# BB8_PCB.net
KiCad netlist of a schematic drawn in EAGLE
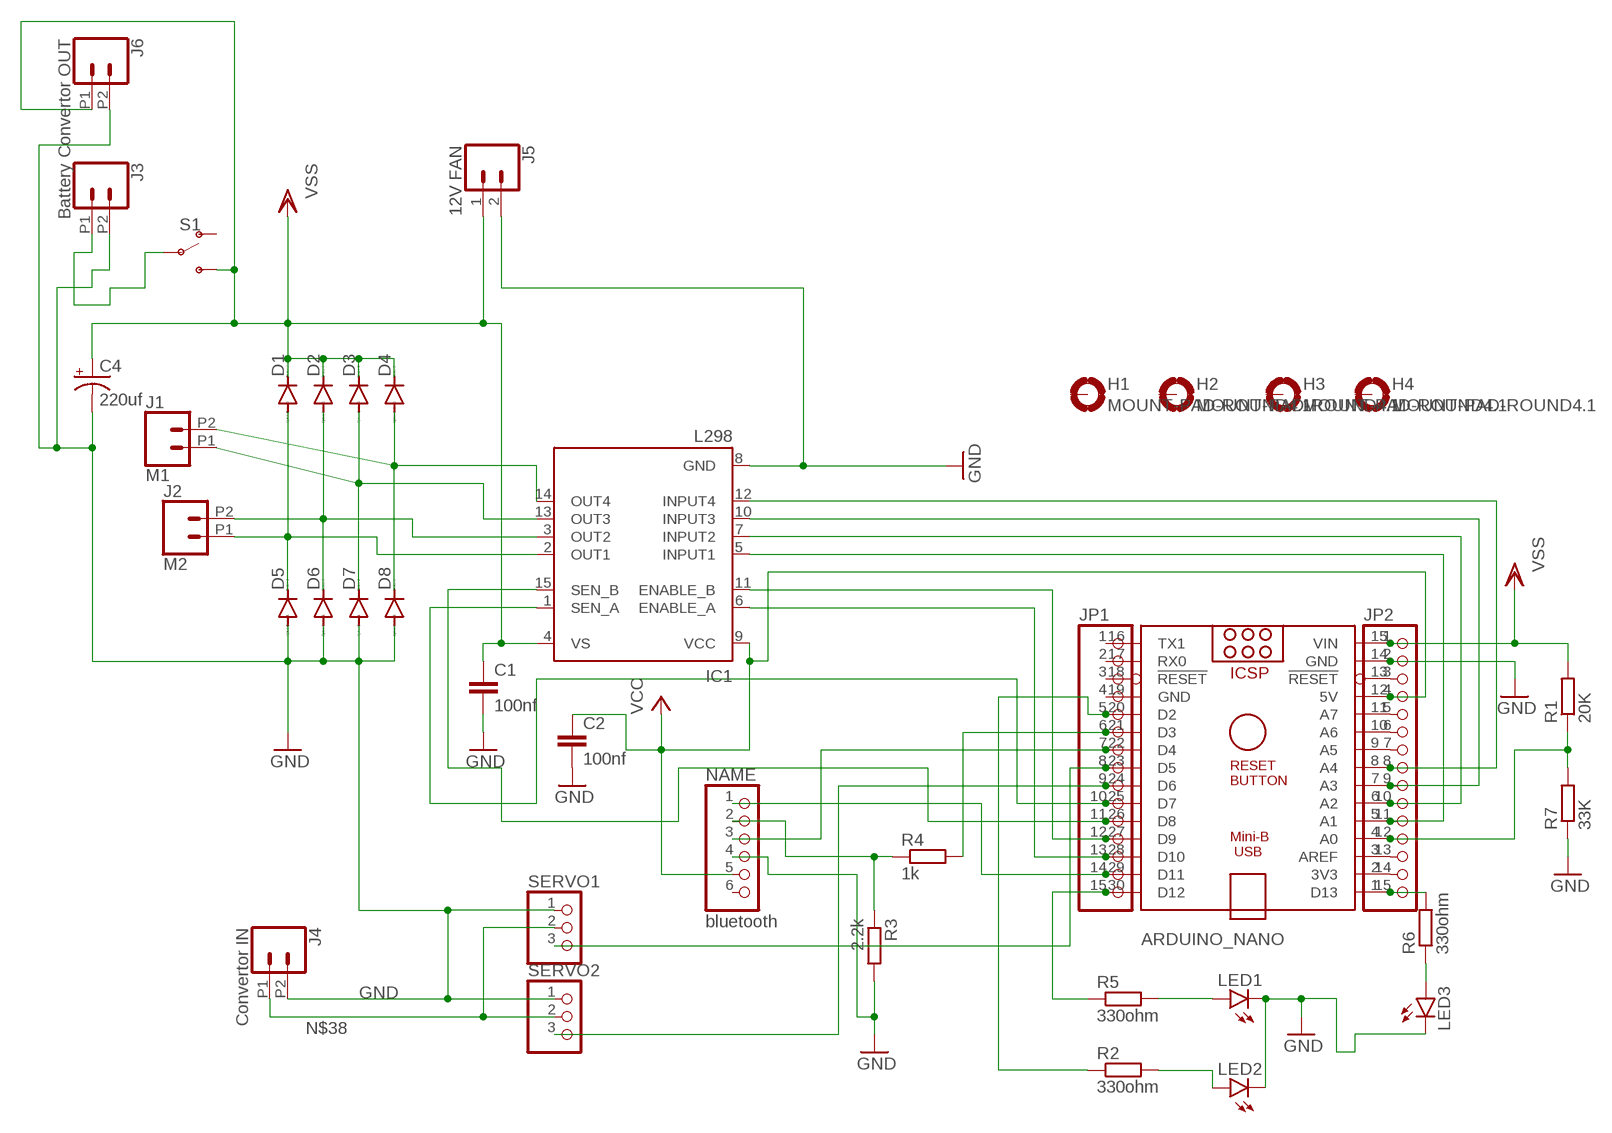
[diagram p0: schematic, sheet 1]

(export (version "E")
  (design (tool "Eeschema 10.0.6"))
  (components
    (comp (ref "ARDUINO_NANO")
      (value "ARDUINO_NANO")
      (footprint "eagle-import:ARDUINO_NANO")
      (libsource (lib "eagle-import") (part "ARDUINO_NANO"))
    )
    (comp (ref "BLUETOOTH")
      (value "bluetooth")
      (footprint "eagle-import:1X06")
      (libsource (lib "eagle-import") (part "PINHD-1X6"))
    )
    (comp (ref "C1")
      (value "100nf")
      (footprint "eagle-import:C5B2.5")
      (libsource (lib "eagle-import") (part "C5/2.5"))
    )
    (comp (ref "C2")
      (value "100nf")
      (footprint "eagle-import:C5B2.5")
      (libsource (lib "eagle-import") (part "C5/2.5"))
    )
    (comp (ref "C4")
      (value "220uf")
      (footprint "eagle-import:E5-8,5")
      (libsource (lib "eagle-import") (part "CPOL-USE5-8.5"))
    )
    (comp (ref "D1")
      (value "1N4148DO35-7")
      (footprint "eagle-import:DO35-7")
      (libsource (lib "eagle-import") (part "1N4148DO35-7"))
    )
    (comp (ref "D2")
      (value "1N4148DO35-7")
      (footprint "eagle-import:DO35-7")
      (libsource (lib "eagle-import") (part "1N4148DO35-7"))
    )
    (comp (ref "D3")
      (value "1N4148DO35-7")
      (footprint "eagle-import:DO35-7")
      (libsource (lib "eagle-import") (part "1N4148DO35-7"))
    )
    (comp (ref "D4")
      (value "1N4148DO35-7")
      (footprint "eagle-import:DO35-7")
      (libsource (lib "eagle-import") (part "1N4148DO35-7"))
    )
    (comp (ref "D5")
      (value "1N4148DO35-7")
      (footprint "eagle-import:DO35-7")
      (libsource (lib "eagle-import") (part "1N4148DO35-7"))
    )
    (comp (ref "D6")
      (value "1N4148DO35-7")
      (footprint "eagle-import:DO35-7")
      (libsource (lib "eagle-import") (part "1N4148DO35-7"))
    )
    (comp (ref "D7")
      (value "1N4148DO35-7")
      (footprint "eagle-import:DO35-7")
      (libsource (lib "eagle-import") (part "1N4148DO35-7"))
    )
    (comp (ref "D8")
      (value "1N4148DO35-7")
      (footprint "eagle-import:DO35-7")
      (libsource (lib "eagle-import") (part "1N4148DO35-7"))
    )
    (comp (ref "H1")
      (value "MOUNT-PAD-ROUND4.1")
      (footprint "eagle-import:4,1-PAD")
      (libsource (lib "eagle-import") (part "MOUNT-PAD-ROUND4.1"))
    )
    (comp (ref "H2")
      (value "MOUNT-PAD-ROUND4.1")
      (footprint "eagle-import:4,1-PAD")
      (libsource (lib "eagle-import") (part "MOUNT-PAD-ROUND4.1"))
    )
    (comp (ref "H3")
      (value "MOUNT-PAD-ROUND4.1")
      (footprint "eagle-import:4,1-PAD")
      (libsource (lib "eagle-import") (part "MOUNT-PAD-ROUND4.1"))
    )
    (comp (ref "H4")
      (value "MOUNT-PAD-ROUND4.1")
      (footprint "eagle-import:4,1-PAD")
      (libsource (lib "eagle-import") (part "MOUNT-PAD-ROUND4.1"))
    )
    (comp (ref "IC1")
      (value "L298")
      (footprint "eagle-import:MULTIWATT-15")
      (fields (field (name "MPN") "L298N"))
      (libsource (lib "eagle-import") (part "L298"))
    )
    (comp (ref "J1")
      (value "M1")
      (footprint "eagle-import:1X02_2.54_SCREWTERM")
      (libsource (lib "eagle-import") (part "CONN_022.54MM_SCREWTERM"))
    )
    (comp (ref "J2")
      (value "M2")
      (footprint "eagle-import:1X02_2.54_SCREWTERM")
      (libsource (lib "eagle-import") (part "CONN_022.54MM_SCREWTERM"))
    )
    (comp (ref "J3")
      (value "Battery")
      (footprint "eagle-import:1X02_2.54_SCREWTERM")
      (libsource (lib "eagle-import") (part "CONN_022.54MM_SCREWTERM"))
    )
    (comp (ref "J4")
      (value "Convertor IN")
      (footprint "eagle-import:1X02_2.54_SCREWTERM")
      (libsource (lib "eagle-import") (part "CONN_022.54MM_SCREWTERM"))
    )
    (comp (ref "J5")
      (value "12V FAN")
      (footprint "eagle-import:1X02")
      (libsource (lib "eagle-import") (part "CONN_02"))
    )
    (comp (ref "J6")
      (value "Convertor OUT")
      (footprint "eagle-import:1X02_2.54_SCREWTERM")
      (libsource (lib "eagle-import") (part "CONN_022.54MM_SCREWTERM"))
    )
    (comp (ref "JP1")
      (value "PINHD-1X15")
      (footprint "eagle-import:1X15")
      (libsource (lib "eagle-import") (part "PINHD-1X15"))
    )
    (comp (ref "JP2")
      (value "PINHD-1X15")
      (footprint "eagle-import:1X15")
      (libsource (lib "eagle-import") (part "PINHD-1X15"))
    )
    (comp (ref "LED1")
      (value "LED5MM")
      (footprint "eagle-import:LED5MM")
      (libsource (lib "eagle-import") (part "LED5MM"))
    )
    (comp (ref "LED2")
      (value "LED5MM")
      (footprint "eagle-import:LED5MM")
      (libsource (lib "eagle-import") (part "LED5MM"))
    )
    (comp (ref "LED3")
      (value "LED5MM")
      (footprint "eagle-import:LED5MM")
      (libsource (lib "eagle-import") (part "LED5MM"))
    )
    (comp (ref "R1")
      (value "20K")
      (footprint "eagle-import:0204_7")
      (libsource (lib "eagle-import") (part "R-EU_0204/7"))
    )
    (comp (ref "R2")
      (value "330ohm")
      (footprint "eagle-import:0204_7")
      (libsource (lib "eagle-import") (part "R-EU_0204/7"))
    )
    (comp (ref "R3")
      (value "2.2k")
      (footprint "eagle-import:0204_7")
      (libsource (lib "eagle-import") (part "R-EU_0204/7"))
    )
    (comp (ref "R4")
      (value "1k")
      (footprint "eagle-import:0204_7")
      (libsource (lib "eagle-import") (part "R-EU_0204/7"))
    )
    (comp (ref "R5")
      (value "330ohm")
      (footprint "eagle-import:0204_7")
      (libsource (lib "eagle-import") (part "R-EU_0204/7"))
    )
    (comp (ref "R6")
      (value "330ohm")
      (footprint "eagle-import:0204_7")
      (libsource (lib "eagle-import") (part "R-EU_0204/7"))
    )
    (comp (ref "R7")
      (value "33K")
      (footprint "eagle-import:0204_7")
      (libsource (lib "eagle-import") (part "R-EU_0204/7"))
    )
    (comp (ref "S1")
      (value "SWITCH-SPDT-PTH-11.6X4.0MM-LOCK")
      (footprint "eagle-import:SWITCH_SPDT_PTH_11.6X4.0MM_LOCK")
      (libsource (lib "eagle-import") (part "SWITCH-SPDT-PTH-11.6X4.0MM-LOCK"))
    )
    (comp (ref "SERVO1")
      (value "PINHD-1X3")
      (footprint "eagle-import:1X03")
      (libsource (lib "eagle-import") (part "PINHD-1X3"))
    )
    (comp (ref "SERVO2")
      (value "PINHD-1X3")
      (footprint "eagle-import:1X03")
      (libsource (lib "eagle-import") (part "PINHD-1X3"))
    )
  )
  (nets
    (net (code "1") (name "/N$38") (class "Default")
      (node (ref "J4") (pin "P1") (pinfunction "1_P1") (pintype "passive"))
      (node (ref "SERVO1") (pin "2") (pinfunction "2_2") (pintype "passive"))
      (node (ref "SERVO2") (pin "2") (pinfunction "2_2") (pintype "passive"))
    )
    (net (code "2") (name "GND") (class "Default")
      (node (ref "ARDUINO_NANO") (pin "14") (pinfunction "GND_14") (pintype "power_in"))
      (node (ref "BLUETOOTH") (pin "4") (pinfunction "4_4") (pintype "passive"))
      (node (ref "C1") (pin "2") (pinfunction "2_2") (pintype "passive"))
      (node (ref "C2") (pin "2") (pinfunction "2_2") (pintype "passive"))
      (node (ref "C4") (pin "-") (pinfunction "-_-") (pintype "passive"))
      (node (ref "D5") (pin "A") (pinfunction "A_A") (pintype "passive"))
      (node (ref "D6") (pin "A") (pinfunction "A_A") (pintype "passive"))
      (node (ref "D7") (pin "A") (pinfunction "A_A") (pintype "passive"))
      (node (ref "D8") (pin "A") (pinfunction "A_A") (pintype "passive"))
      (node (ref "IC1") (pin "8") (pinfunction "GND_8") (pintype "power_in"))
      (node (ref "J3") (pin "P2") (pinfunction "2_P2") (pintype "passive"))
      (node (ref "J4") (pin "P2") (pinfunction "2_P2") (pintype "passive"))
      (node (ref "J5") (pin "2") (pinfunction "2_2") (pintype "passive"))
      (node (ref "J6") (pin "P2") (pinfunction "2_P2") (pintype "passive"))
      (node (ref "JP2") (pin "2") (pinfunction "2_2") (pintype "passive"))
      (node (ref "LED1") (pin "K") (pinfunction "C_K") (pintype "passive"))
      (node (ref "LED2") (pin "K") (pinfunction "C_K") (pintype "passive"))
      (node (ref "LED3") (pin "K") (pinfunction "C_K") (pintype "passive"))
      (node (ref "R3") (pin "2") (pinfunction "2_2") (pintype "passive"))
      (node (ref "R7") (pin "1") (pinfunction "1_1") (pintype "passive"))
      (node (ref "SERVO1") (pin "1") (pinfunction "1_1") (pintype "passive"))
      (node (ref "SERVO2") (pin "1") (pinfunction "1_1") (pintype "passive"))
    )
    (net (code "3") (name "Net-(ARDUINO_NANO-3V3)") (class "Default")
      (node (ref "ARDUINO_NANO") (pin "2") (pinfunction "3V3_2") (pintype "output"))
      (node (ref "JP2") (pin "14") (pinfunction "14_14") (pintype "passive"))
    )
    (net (code "4") (name "Net-(ARDUINO_NANO-A0)") (class "Default")
      (node (ref "ARDUINO_NANO") (pin "4") (pinfunction "A0_4") (pintype "bidirectional"))
      (node (ref "JP2") (pin "12") (pinfunction "12_12") (pintype "passive"))
      (node (ref "R1") (pin "1") (pinfunction "1_1") (pintype "passive"))
      (node (ref "R7") (pin "2") (pinfunction "2_2") (pintype "passive"))
    )
    (net (code "5") (name "Net-(ARDUINO_NANO-A1)") (class "Default")
      (node (ref "ARDUINO_NANO") (pin "5") (pinfunction "A1_5") (pintype "bidirectional"))
      (node (ref "IC1") (pin "5") (pinfunction "INPUT1_5") (pintype "input"))
      (node (ref "JP2") (pin "11") (pinfunction "11_11") (pintype "passive"))
    )
    (net (code "6") (name "Net-(ARDUINO_NANO-A2)") (class "Default")
      (node (ref "ARDUINO_NANO") (pin "6") (pinfunction "A2_6") (pintype "bidirectional"))
      (node (ref "IC1") (pin "7") (pinfunction "INPUT2_7") (pintype "input"))
      (node (ref "JP2") (pin "10") (pinfunction "10_10") (pintype "passive"))
    )
    (net (code "7") (name "Net-(ARDUINO_NANO-A3)") (class "Default")
      (node (ref "ARDUINO_NANO") (pin "7") (pinfunction "A3_7") (pintype "bidirectional"))
      (node (ref "IC1") (pin "10") (pinfunction "INPUT3_10") (pintype "input"))
      (node (ref "JP2") (pin "9") (pinfunction "9_9") (pintype "passive"))
    )
    (net (code "8") (name "Net-(ARDUINO_NANO-A4)") (class "Default")
      (node (ref "ARDUINO_NANO") (pin "8") (pinfunction "A4_8") (pintype "bidirectional"))
      (node (ref "IC1") (pin "12") (pinfunction "INPUT4_12") (pintype "input"))
      (node (ref "JP2") (pin "8") (pinfunction "8_8") (pintype "passive"))
    )
    (net (code "9") (name "Net-(ARDUINO_NANO-A5)") (class "Default")
      (node (ref "ARDUINO_NANO") (pin "9") (pinfunction "A5_9") (pintype "bidirectional"))
      (node (ref "JP2") (pin "7") (pinfunction "7_7") (pintype "passive"))
    )
    (net (code "10") (name "Net-(ARDUINO_NANO-A6)") (class "Default")
      (node (ref "ARDUINO_NANO") (pin "10") (pinfunction "A6_10") (pintype "bidirectional"))
      (node (ref "JP2") (pin "6") (pinfunction "6_6") (pintype "passive"))
    )
    (net (code "11") (name "Net-(ARDUINO_NANO-A7)") (class "Default")
      (node (ref "ARDUINO_NANO") (pin "11") (pinfunction "A7_11") (pintype "bidirectional"))
      (node (ref "JP2") (pin "5") (pinfunction "5_5") (pintype "passive"))
    )
    (net (code "12") (name "Net-(ARDUINO_NANO-AREF)") (class "Default")
      (node (ref "ARDUINO_NANO") (pin "3") (pinfunction "AREF_3") (pintype "input"))
      (node (ref "JP2") (pin "13") (pinfunction "13_13") (pintype "passive"))
    )
    (net (code "13") (name "Net-(ARDUINO_NANO-D2)") (class "Default")
      (node (ref "ARDUINO_NANO") (pin "20") (pinfunction "D2_20") (pintype "bidirectional"))
      (node (ref "JP1") (pin "5") (pinfunction "5_5") (pintype "passive"))
      (node (ref "R2") (pin "1") (pinfunction "1_1") (pintype "passive"))
    )
    (net (code "14") (name "Net-(ARDUINO_NANO-D3)") (class "Default")
      (node (ref "ARDUINO_NANO") (pin "21") (pinfunction "D3_21") (pintype "bidirectional"))
      (node (ref "JP1") (pin "6") (pinfunction "6_6") (pintype "passive"))
      (node (ref "R4") (pin "2") (pinfunction "2_2") (pintype "passive"))
    )
    (net (code "15") (name "Net-(ARDUINO_NANO-D4)") (class "Default")
      (node (ref "ARDUINO_NANO") (pin "22") (pinfunction "D4_22") (pintype "bidirectional"))
      (node (ref "BLUETOOTH") (pin "3") (pinfunction "3_3") (pintype "passive"))
      (node (ref "JP1") (pin "7") (pinfunction "7_7") (pintype "passive"))
    )
    (net (code "16") (name "Net-(ARDUINO_NANO-D5)") (class "Default")
      (node (ref "ARDUINO_NANO") (pin "23") (pinfunction "D5_23") (pintype "bidirectional"))
      (node (ref "JP1") (pin "8") (pinfunction "8_8") (pintype "passive"))
      (node (ref "SERVO1") (pin "3") (pinfunction "3_3") (pintype "passive"))
    )
    (net (code "17") (name "Net-(ARDUINO_NANO-D6)") (class "Default")
      (node (ref "ARDUINO_NANO") (pin "24") (pinfunction "D6_24") (pintype "bidirectional"))
      (node (ref "JP1") (pin "9") (pinfunction "9_9") (pintype "passive"))
      (node (ref "SERVO2") (pin "3") (pinfunction "3_3") (pintype "passive"))
    )
    (net (code "18") (name "Net-(ARDUINO_NANO-D7)") (class "Default")
      (node (ref "ARDUINO_NANO") (pin "25") (pinfunction "D7_25") (pintype "bidirectional"))
      (node (ref "IC1") (pin "1") (pinfunction "SEN_A_1") (pintype "input"))
      (node (ref "JP1") (pin "10") (pinfunction "10_10") (pintype "passive"))
    )
    (net (code "19") (name "Net-(ARDUINO_NANO-D8)") (class "Default")
      (node (ref "ARDUINO_NANO") (pin "26") (pinfunction "D8_26") (pintype "bidirectional"))
      (node (ref "IC1") (pin "15") (pinfunction "SEN_B_15") (pintype "input"))
      (node (ref "JP1") (pin "11") (pinfunction "11_11") (pintype "passive"))
    )
    (net (code "20") (name "Net-(ARDUINO_NANO-D9)") (class "Default")
      (node (ref "ARDUINO_NANO") (pin "27") (pinfunction "D9_27") (pintype "bidirectional"))
      (node (ref "IC1") (pin "11") (pinfunction "ENABLE_B_11") (pintype "input"))
      (node (ref "JP1") (pin "12") (pinfunction "12_12") (pintype "passive"))
    )
    (net (code "21") (name "Net-(ARDUINO_NANO-D10)") (class "Default")
      (node (ref "ARDUINO_NANO") (pin "28") (pinfunction "D10_28") (pintype "bidirectional"))
      (node (ref "IC1") (pin "6") (pinfunction "ENABLE_A_6") (pintype "input"))
      (node (ref "JP1") (pin "13") (pinfunction "13_13") (pintype "passive"))
    )
    (net (code "22") (name "Net-(ARDUINO_NANO-D11)") (class "Default")
      (node (ref "ARDUINO_NANO") (pin "29") (pinfunction "D11_29") (pintype "bidirectional"))
      (node (ref "BLUETOOTH") (pin "1") (pinfunction "1_1") (pintype "passive"))
      (node (ref "JP1") (pin "14") (pinfunction "14_14") (pintype "passive"))
    )
    (net (code "23") (name "Net-(ARDUINO_NANO-D12)") (class "Default")
      (node (ref "ARDUINO_NANO") (pin "30") (pinfunction "D12_30") (pintype "bidirectional"))
      (node (ref "JP1") (pin "15") (pinfunction "15_15") (pintype "passive"))
      (node (ref "R5") (pin "1") (pinfunction "1_1") (pintype "passive"))
    )
    (net (code "24") (name "Net-(ARDUINO_NANO-D13)") (class "Default")
      (node (ref "ARDUINO_NANO") (pin "1") (pinfunction "D13_1") (pintype "bidirectional"))
      (node (ref "JP2") (pin "15") (pinfunction "15_15") (pintype "passive"))
      (node (ref "R6") (pin "2") (pinfunction "2_2") (pintype "passive"))
    )
    (net (code "25") (name "Net-(ARDUINO_NANO-GND-Pad19)") (class "Default")
      (node (ref "ARDUINO_NANO") (pin "19") (pinfunction "GND_19") (pintype "power_in"))
      (node (ref "JP1") (pin "4") (pinfunction "4_4") (pintype "passive"))
    )
    (net (code "26") (name "Net-(ARDUINO_NANO-RX0)") (class "Default")
      (node (ref "ARDUINO_NANO") (pin "17") (pinfunction "RX0_17") (pintype "bidirectional"))
      (node (ref "JP1") (pin "2") (pinfunction "2_2") (pintype "passive"))
    )
    (net (code "27") (name "Net-(ARDUINO_NANO-TX1)") (class "Default")
      (node (ref "ARDUINO_NANO") (pin "16") (pinfunction "TX1_16") (pintype "bidirectional"))
      (node (ref "JP1") (pin "1") (pinfunction "1_1") (pintype "passive"))
    )
    (net (code "28") (name "Net-(ARDUINO_NANO-~{RESET}-Pad13)") (class "Default")
      (node (ref "ARDUINO_NANO") (pin "13") (pinfunction "~{RESET}_13") (pintype "input"))
      (node (ref "JP2") (pin "3") (pinfunction "3_3") (pintype "passive"))
    )
    (net (code "29") (name "Net-(ARDUINO_NANO-~{RESET}-Pad18)") (class "Default")
      (node (ref "ARDUINO_NANO") (pin "18") (pinfunction "~{RESET}_18") (pintype "input"))
      (node (ref "JP1") (pin "3") (pinfunction "3_3") (pintype "passive"))
    )
    (net (code "30") (name "Net-(BLUETOOTH-Pad2)") (class "Default")
      (node (ref "BLUETOOTH") (pin "2") (pinfunction "2_2") (pintype "passive"))
      (node (ref "R3") (pin "1") (pinfunction "1_1") (pintype "passive"))
      (node (ref "R4") (pin "1") (pinfunction "1_1") (pintype "passive"))
    )
    (net (code "31") (name "Net-(IC1-OUT1)") (class "Default")
      (node (ref "D1") (pin "A") (pinfunction "A_A") (pintype "passive"))
      (node (ref "D5") (pin "C") (pinfunction "C_C") (pintype "passive"))
      (node (ref "IC1") (pin "2") (pinfunction "OUT1_2") (pintype "output"))
      (node (ref "J2") (pin "P1") (pinfunction "1_P1") (pintype "passive"))
    )
    (net (code "32") (name "Net-(IC1-OUT2)") (class "Default")
      (node (ref "D2") (pin "A") (pinfunction "A_A") (pintype "passive"))
      (node (ref "D6") (pin "C") (pinfunction "C_C") (pintype "passive"))
      (node (ref "IC1") (pin "3") (pinfunction "OUT2_3") (pintype "output"))
      (node (ref "J2") (pin "P2") (pinfunction "2_P2") (pintype "passive"))
    )
    (net (code "33") (name "Net-(IC1-OUT3)") (class "Default")
      (node (ref "D3") (pin "A") (pinfunction "A_A") (pintype "passive"))
      (node (ref "D7") (pin "C") (pinfunction "C_C") (pintype "passive"))
      (node (ref "IC1") (pin "13") (pinfunction "OUT3_13") (pintype "output"))
      (node (ref "J1") (pin "P1") (pinfunction "1_P1") (pintype "passive"))
    )
    (net (code "34") (name "Net-(IC1-OUT4)") (class "Default")
      (node (ref "D4") (pin "A") (pinfunction "A_A") (pintype "passive"))
      (node (ref "D8") (pin "C") (pinfunction "C_C") (pintype "passive"))
      (node (ref "IC1") (pin "14") (pinfunction "OUT4_14") (pintype "output"))
      (node (ref "J1") (pin "P2") (pinfunction "2_P2") (pintype "passive"))
    )
    (net (code "35") (name "Net-(J3-1)") (class "Default")
      (node (ref "J3") (pin "P1") (pinfunction "1_P1") (pintype "passive"))
      (node (ref "S1") (pin "2") (pinfunction "P_2") (pintype "passive"))
    )
    (net (code "36") (name "Net-(LED1-PadA)") (class "Default")
      (node (ref "LED1") (pin "A") (pinfunction "A_A") (pintype "passive"))
      (node (ref "R5") (pin "2") (pinfunction "2_2") (pintype "passive"))
    )
    (net (code "37") (name "Net-(LED2-PadA)") (class "Default")
      (node (ref "LED2") (pin "A") (pinfunction "A_A") (pintype "passive"))
      (node (ref "R2") (pin "2") (pinfunction "2_2") (pintype "passive"))
    )
    (net (code "38") (name "Net-(LED3-PadA)") (class "Default")
      (node (ref "LED3") (pin "A") (pinfunction "A_A") (pintype "passive"))
      (node (ref "R6") (pin "1") (pinfunction "1_1") (pintype "passive"))
    )
    (net (code "39") (name "VCC") (class "Default")
      (node (ref "ARDUINO_NANO") (pin "12") (pinfunction "5V_12") (pintype "power_in"))
      (node (ref "BLUETOOTH") (pin "5") (pinfunction "5_5") (pintype "passive"))
      (node (ref "C2") (pin "1") (pinfunction "1_1") (pintype "passive"))
      (node (ref "IC1") (pin "9") (pinfunction "VCC_9") (pintype "power_in"))
      (node (ref "JP2") (pin "4") (pinfunction "4_4") (pintype "passive"))
    )
    (net (code "40") (name "VSS") (class "Default")
      (node (ref "ARDUINO_NANO") (pin "15") (pinfunction "VIN_15") (pintype "power_in"))
      (node (ref "C1") (pin "1") (pinfunction "1_1") (pintype "passive"))
      (node (ref "C4") (pin "+") (pinfunction "+_+") (pintype "passive"))
      (node (ref "D1") (pin "C") (pinfunction "C_C") (pintype "passive"))
      (node (ref "D2") (pin "C") (pinfunction "C_C") (pintype "passive"))
      (node (ref "D3") (pin "C") (pinfunction "C_C") (pintype "passive"))
      (node (ref "D4") (pin "C") (pinfunction "C_C") (pintype "passive"))
      (node (ref "IC1") (pin "4") (pinfunction "VS_4") (pintype "power_in"))
      (node (ref "J5") (pin "1") (pinfunction "1_1") (pintype "passive"))
      (node (ref "J6") (pin "P1") (pinfunction "1_P1") (pintype "passive"))
      (node (ref "JP2") (pin "1") (pinfunction "1_1") (pintype "passive"))
      (node (ref "R1") (pin "2") (pinfunction "2_2") (pintype "passive"))
      (node (ref "S1") (pin "3") (pinfunction "S_3") (pintype "passive"))
    )
    (net (code "41") (name "unconnected-(BLUETOOTH-Pad6)") (class "Default")
      (node (ref "BLUETOOTH") (pin "6") (pinfunction "6_6") (pintype "passive"))
    )
    (net (code "42") (name "unconnected-(H1-MOUNT-PadB4,1)") (class "Default")
      (node (ref "H1") (pin "B4,1") (pinfunction "MOUNT_B4,1") (pintype "passive"))
    )
    (net (code "43") (name "unconnected-(H2-MOUNT-PadB4,1)") (class "Default")
      (node (ref "H2") (pin "B4,1") (pinfunction "MOUNT_B4,1") (pintype "passive"))
    )
    (net (code "44") (name "unconnected-(H3-MOUNT-PadB4,1)") (class "Default")
      (node (ref "H3") (pin "B4,1") (pinfunction "MOUNT_B4,1") (pintype "passive"))
    )
    (net (code "45") (name "unconnected-(H4-MOUNT-PadB4,1)") (class "Default")
      (node (ref "H4") (pin "B4,1") (pinfunction "MOUNT_B4,1") (pintype "passive"))
    )
    (net (code "46") (name "unconnected-(S1-O-Pad1)") (class "Default")
      (node (ref "S1") (pin "1") (pinfunction "O_1") (pintype "passive"))
    )
  )
)
